# MCU2S_copy.net
KiCad netlist of a schematic drawn in Altium Designer
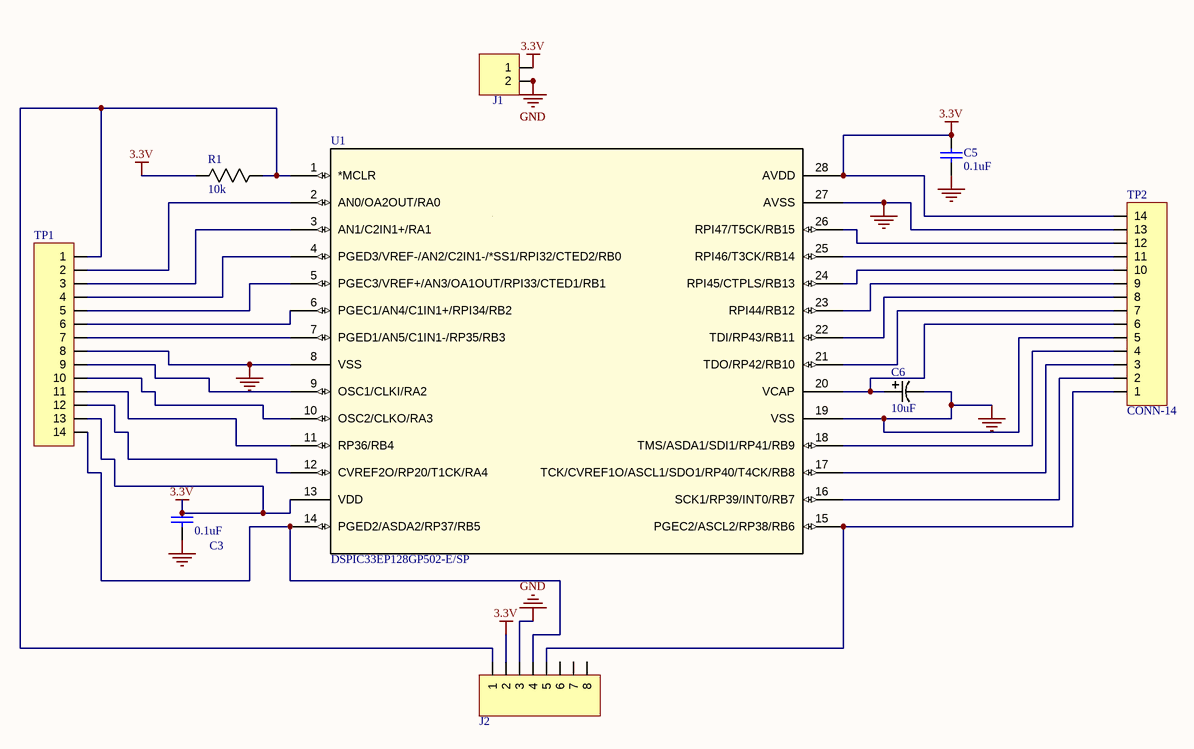
[diagram p0: MCU2S copy.SchDoc]

(export (version "E")
  (design (tool "Eeschema 10.0.6"))
  (components
    (comp (ref "C3")
      (value "0.1uF")
      (footprint "0603")
      (description "CAP CER 0.1UF 250V X7R 1206")
      (fields (field (name "Comment") "C1206C104KARACTU"))
      (libsource (lib "JL_PCBlib") (part "C1206C104KARACTU"))
    )
    (comp (ref "C5")
      (value "0.1uF")
      (footprint "0603")
      (description "CAP CER 0.1UF 250V X7R 1206")
      (fields (field (name "Comment") "C1206C104KARACTU"))
      (libsource (lib "JL_PCBlib") (part "C1206C104KARACTU"))
    )
    (comp (ref "C6")
      (value "10uF")
      (footprint "TAJA106M010RNJ")
      (description "CAP TANT 10UF 20% 10V 1206")
      (fields (field (name "Comment") "TAJA106M010RNJ"))
      (libsource (lib "JL_PCBlib") (part "TAJA106M010RNJ"))
    )
    (comp (ref "J1") (value "CONN-2") (footprint "CONN-2") (libsource (lib "JL_PCBlib") (part "CONN-2")))
    (comp (ref "J2")
      (value "CONN-8")
      (footprint "CONN-8")
      (description "J?")
      (libsource (lib "JL_PCBlib") (part "CONN-8"))
    )
    (comp (ref "R1")
      (value "10k")
      (footprint "0805")
      (description "10 kOhms ±1% 0.125W, 1/8W Chip Resistor 0805 (2012 Metric) Automotive AEC-Q200 Thick Film")
      (fields (field (name "Comment") "RES 10K OHM 1% 1/8W 0805"))
      (libsource (lib "JL_PCBlib") (part "RMCF0805FT10K0"))
    )
    (comp (ref "TP1") (value "~") (footprint "CONN-14") (libsource (lib "JL_PCBlib") (part "CONN-14")))
    (comp (ref "TP2") (value "CONN-14") (footprint "CONN-14") (libsource (lib "") (part "CONN-14_1")))
    (comp (ref "U1")
      (value "DSPIC33EP128GP502-E/SP")
      (footprint "DSPIC33EP128GP502")
      (description "IC MCU 16BIT 128KB FLASH 28SPDIP")
      (libsource (lib "JL_PCBlib") (part "DSPIC33EP128GP502-E/SP"))
    )
  )
  (nets
    (net (code "1") (name "3.3V") (class "Default")
      (node (ref "C3") (pin "2") (pinfunction "2_2") (pintype "passive"))
      (node (ref "C5") (pin "2") (pinfunction "2_2") (pintype "passive"))
      (node (ref "J1") (pin "1") (pinfunction "1_1") (pintype "passive"))
      (node (ref "J2") (pin "2") (pinfunction "2_2") (pintype "passive"))
      (node (ref "R1") (pin "1") (pinfunction "1_1") (pintype "passive"))
      (node (ref "TP1") (pin "13") (pinfunction "13_13") (pintype "passive"))
      (node (ref "TP2") (pin "14") (pinfunction "14_14") (pintype "passive"))
      (node (ref "U1") (pin "13") (pinfunction "VDD_13") (pintype "power_in"))
      (node (ref "U1") (pin "28") (pinfunction "AVDD_28") (pintype "power_in"))
    )
    (net (code "2") (name "GND") (class "Default")
      (node (ref "C3") (pin "1") (pinfunction "1_1") (pintype "passive"))
      (node (ref "C5") (pin "1") (pinfunction "1_1") (pintype "passive"))
      (node (ref "C6") (pin "2") (pinfunction "2_2") (pintype "passive"))
      (node (ref "J1") (pin "2") (pinfunction "2_2") (pintype "passive"))
      (node (ref "J2") (pin "3") (pinfunction "3_3") (pintype "passive"))
      (node (ref "TP1") (pin "8") (pinfunction "8_8") (pintype "passive"))
      (node (ref "TP2") (pin "13") (pinfunction "13_13") (pintype "passive"))
      (node (ref "TP2") (pin "5") (pinfunction "5_5") (pintype "passive"))
      (node (ref "U1") (pin "19") (pinfunction "VSS_19") (pintype "power_in"))
      (node (ref "U1") (pin "27") (pinfunction "AVSS_27") (pintype "power_in"))
      (node (ref "U1") (pin "8") (pinfunction "VSS_8") (pintype "power_in"))
    )
    (net (code "3") (name "Net-(U1-*MCLR)") (class "Default")
      (node (ref "J2") (pin "1") (pinfunction "1_1") (pintype "passive"))
      (node (ref "R1") (pin "2") (pinfunction "2_2") (pintype "passive"))
      (node (ref "TP1") (pin "1") (pinfunction "1_1") (pintype "passive"))
      (node (ref "U1") (pin "1") (pinfunction "*MCLR_1") (pintype "bidirectional"))
    )
    (net (code "4") (name "Net-(U1-AN0{slash}OA2OUT{slash}RA0)") (class "Default")
      (node (ref "TP1") (pin "2") (pinfunction "2_2") (pintype "passive"))
      (node (ref "U1") (pin "2") (pinfunction "AN0/OA2OUT/RA0_2") (pintype "bidirectional"))
    )
    (net (code "5") (name "Net-(U1-AN1{slash}C2IN1+{slash}RA1)") (class "Default")
      (node (ref "TP1") (pin "3") (pinfunction "3_3") (pintype "passive"))
      (node (ref "U1") (pin "3") (pinfunction "AN1/C2IN1+/RA1_3") (pintype "bidirectional"))
    )
    (net (code "6") (name "Net-(U1-CVREF2O{slash}RP20{slash}T1CK{slash}RA4)") (class "Default")
      (node (ref "TP1") (pin "12") (pinfunction "12_12") (pintype "passive"))
      (node (ref "U1") (pin "12") (pinfunction "CVREF2O/RP20/T1CK/RA4_12") (pintype "bidirectional"))
    )
    (net (code "7") (name "Net-(U1-OSC1{slash}CLKI{slash}RA2)") (class "Default")
      (node (ref "TP1") (pin "9") (pinfunction "9_9") (pintype "passive"))
      (node (ref "U1") (pin "9") (pinfunction "OSC1/CLKI/RA2_9") (pintype "bidirectional"))
    )
    (net (code "8") (name "Net-(U1-OSC2{slash}CLKO{slash}RA3)") (class "Default")
      (node (ref "TP1") (pin "10") (pinfunction "10_10") (pintype "passive"))
      (node (ref "U1") (pin "10") (pinfunction "OSC2/CLKO/RA3_10") (pintype "bidirectional"))
    )
    (net (code "9") (name "Net-(U1-PGEC1{slash}AN4{slash}C1IN1+{slash}RPI34{slash}RB2)") (class "Default")
      (node (ref "TP1") (pin "6") (pinfunction "6_6") (pintype "passive"))
      (node (ref "U1") (pin "6") (pinfunction "PGEC1/AN4/C1IN1+/RPI34/RB2_6") (pintype "bidirectional"))
    )
    (net (code "10") (name "Net-(U1-PGEC2{slash}ASCL2{slash}RP38{slash}RB6)") (class "Default")
      (node (ref "J2") (pin "5") (pinfunction "5_5") (pintype "passive"))
      (node (ref "TP2") (pin "1") (pinfunction "1_1") (pintype "passive"))
      (node (ref "U1") (pin "15") (pinfunction "PGEC2/ASCL2/RP38/RB6_15") (pintype "bidirectional"))
    )
    (net (code "11") (name "Net-(U1-PGEC3{slash}VREF+{slash}AN3{slash}OA1OUT{slash}RPI33{slash}CTED1{slash}RB1)") (class "Default")
      (node (ref "TP1") (pin "5") (pinfunction "5_5") (pintype "passive"))
      (node (ref "U1") (pin "5") (pinfunction "PGEC3/VREF+/AN3/OA1OUT/RPI33/CTED1/RB1_5") (pintype "bidirectional"))
    )
    (net (code "12") (name "Net-(U1-PGED1{slash}AN5{slash}C1IN1-{slash}RP35{slash}RB3)") (class "Default")
      (node (ref "TP1") (pin "7") (pinfunction "7_7") (pintype "passive"))
      (node (ref "U1") (pin "7") (pinfunction "PGED1/AN5/C1IN1-/RP35/RB3_7") (pintype "bidirectional"))
    )
    (net (code "13") (name "Net-(U1-PGED2{slash}ASDA2{slash}RP37{slash}RB5)") (class "Default")
      (node (ref "J2") (pin "4") (pinfunction "4_4") (pintype "passive"))
      (node (ref "TP1") (pin "14") (pinfunction "14_14") (pintype "passive"))
      (node (ref "U1") (pin "14") (pinfunction "PGED2/ASDA2/RP37/RB5_14") (pintype "bidirectional"))
    )
    (net (code "14") (name "Net-(U1-PGED3{slash}VREF-{slash}AN2{slash}C2IN1-{slash}*SS1{slash}RPI32{slash}CTED2{slash}RB0)") (class "Default")
      (node (ref "TP1") (pin "4") (pinfunction "4_4") (pintype "passive"))
      (node (ref "U1") (pin "4") (pinfunction "PGED3/VREF-/AN2/C2IN1-/*SS1/RPI32/CTED2/RB0_4") (pintype "bidirectional"))
    )
    (net (code "15") (name "Net-(U1-RP36{slash}RB4)") (class "Default")
      (node (ref "TP1") (pin "11") (pinfunction "11_11") (pintype "passive"))
      (node (ref "U1") (pin "11") (pinfunction "RP36/RB4_11") (pintype "bidirectional"))
    )
    (net (code "16") (name "Net-(U1-RPI44{slash}RB12)") (class "Default")
      (node (ref "TP2") (pin "9") (pinfunction "9_9") (pintype "passive"))
      (node (ref "U1") (pin "23") (pinfunction "RPI44/RB12_23") (pintype "bidirectional"))
    )
    (net (code "17") (name "Net-(U1-RPI45{slash}CTPLS{slash}RB13)") (class "Default")
      (node (ref "TP2") (pin "10") (pinfunction "10_10") (pintype "passive"))
      (node (ref "U1") (pin "24") (pinfunction "RPI45/CTPLS/RB13_24") (pintype "bidirectional"))
    )
    (net (code "18") (name "Net-(U1-RPI46{slash}T3CK{slash}RB14)") (class "Default")
      (node (ref "TP2") (pin "11") (pinfunction "11_11") (pintype "passive"))
      (node (ref "U1") (pin "25") (pinfunction "RPI46/T3CK/RB14_25") (pintype "bidirectional"))
    )
    (net (code "19") (name "Net-(U1-RPI47{slash}T5CK{slash}RB15)") (class "Default")
      (node (ref "TP2") (pin "12") (pinfunction "12_12") (pintype "passive"))
      (node (ref "U1") (pin "26") (pinfunction "RPI47/T5CK/RB15_26") (pintype "bidirectional"))
    )
    (net (code "20") (name "Net-(U1-SCK1{slash}RP39{slash}INT0{slash}RB7)") (class "Default")
      (node (ref "TP2") (pin "2") (pinfunction "2_2") (pintype "passive"))
      (node (ref "U1") (pin "16") (pinfunction "SCK1/RP39/INT0/RB7_16") (pintype "bidirectional"))
    )
    (net (code "21") (name "Net-(U1-TCK{slash}CVREF1O{slash}ASCL1{slash}SDO1{slash}RP40{slash}T4CK{slash}RB8)") (class "Default")
      (node (ref "TP2") (pin "3") (pinfunction "3_3") (pintype "passive"))
      (node (ref "U1") (pin "17") (pinfunction "TCK/CVREF1O/ASCL1/SDO1/RP40/T4CK/RB8_17") (pintype "bidirectional"))
    )
    (net (code "22") (name "Net-(U1-TDI{slash}RP43{slash}RB11)") (class "Default")
      (node (ref "TP2") (pin "8") (pinfunction "8_8") (pintype "passive"))
      (node (ref "U1") (pin "22") (pinfunction "TDI/RP43/RB11_22") (pintype "bidirectional"))
    )
    (net (code "23") (name "Net-(U1-TDO{slash}RP42{slash}RB10)") (class "Default")
      (node (ref "TP2") (pin "7") (pinfunction "7_7") (pintype "passive"))
      (node (ref "U1") (pin "21") (pinfunction "TDO/RP42/RB10_21") (pintype "bidirectional"))
    )
    (net (code "24") (name "Net-(U1-TMS{slash}ASDA1{slash}SDI1{slash}RP41{slash}RB9)") (class "Default")
      (node (ref "TP2") (pin "4") (pinfunction "4_4") (pintype "passive"))
      (node (ref "U1") (pin "18") (pinfunction "TMS/ASDA1/SDI1/RP41/RB9_18") (pintype "bidirectional"))
    )
    (net (code "25") (name "Net-(U1-VCAP)") (class "Default")
      (node (ref "C6") (pin "1") (pinfunction "1_1") (pintype "passive"))
      (node (ref "TP2") (pin "6") (pinfunction "6_6") (pintype "passive"))
      (node (ref "U1") (pin "20") (pinfunction "VCAP_20") (pintype "power_in"))
    )
    (net (code "26") (name "unconnected-(J2-Pad6)") (class "Default")
      (node (ref "J2") (pin "6") (pinfunction "6_6") (pintype "passive"))
    )
    (net (code "27") (name "unconnected-(J2-Pad7)") (class "Default")
      (node (ref "J2") (pin "7") (pinfunction "7_7") (pintype "passive"))
    )
    (net (code "28") (name "unconnected-(J2-Pad8)") (class "Default")
      (node (ref "J2") (pin "8") (pinfunction "8_8") (pintype "passive"))
    )
  )
)
